# MCU_144.net
KiCad netlist of a schematic drawn in Altium Designer
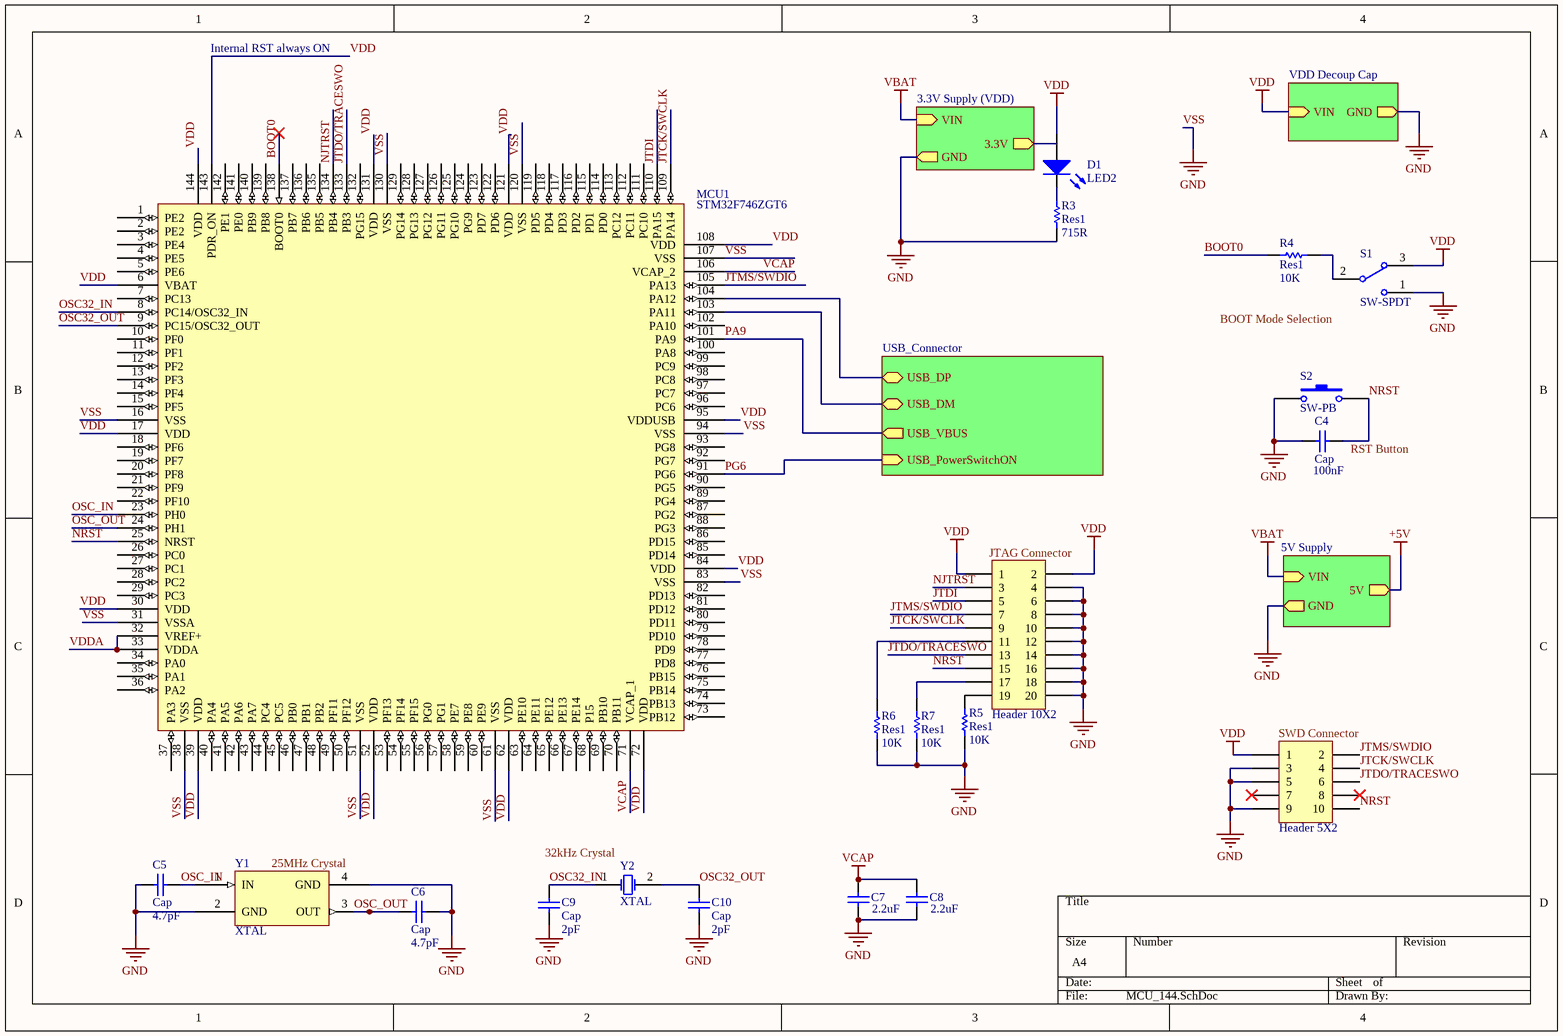
[diagram p0: MCU_144.SchDoc]

(export (version "E")
  (design (tool "Eeschema 10.0.6"))
  (components
    (comp (ref "C4")
      (value "Cap")
      (footprint "0402")
      (description "Multilayer Ceramic Capacitors MLCC - SMD/SMT 16volts 0.1uF 20% X7R")
      (fields (field (name "ALTIUM_VALUE") "100nF"))
      (libsource (lib "Miscellaneous Devices") (part "Cap"))
    )
    (comp (ref "C5")
      (value "Cap")
      (footprint "RAD-0.3")
      (description "Capacitor")
      (fields (field (name "ALTIUM_VALUE") "4.7pF") (field (name "PUBLISHER") "Altium Limited"))
      (libsource (lib "Miscellaneous Devices") (part "Cap"))
    )
    (comp (ref "C6")
      (value "Cap")
      (footprint "RAD-0.3")
      (description "Capacitor")
      (fields (field (name "ALTIUM_VALUE") "4.7pF") (field (name "PUBLISHER") "Altium Limited"))
      (libsource (lib "Miscellaneous Devices") (part "Cap"))
    )
    (comp (ref "C7")
      (value "2.2uF")
      (footprint "0402")
      (description "Multilayer Ceramic Capacitors MLCC - SMD/SMT 0402 2.2uF 6.3volts X5R 10%")
      (fields (field (name "Comment") "Cap"))
      (libsource (lib "Miscellaneous Devices") (part "Cap"))
    )
    (comp (ref "C8")
      (value "2.2uF")
      (footprint "0402")
      (description "Multilayer Ceramic Capacitors MLCC - SMD/SMT 0402 2.2uF 6.3volts X5R 10%")
      (fields (field (name "Comment") "Cap"))
      (libsource (lib "Miscellaneous Devices") (part "Cap"))
    )
    (comp (ref "C9")
      (value "Cap")
      (footprint "RAD-0.3")
      (description "Capacitor")
      (fields (field (name "ALTIUM_VALUE") "2pF") (field (name "PUBLISHER") "Altium Limited"))
      (libsource (lib "Miscellaneous Devices") (part "Cap"))
    )
    (comp (ref "C10")
      (value "Cap")
      (footprint "RAD-0.3")
      (description "Capacitor")
      (fields (field (name "ALTIUM_VALUE") "2pF") (field (name "PUBLISHER") "Altium Limited"))
      (libsource (lib "Miscellaneous Devices") (part "Cap"))
    )
    (comp (ref "D1")
      (value "LED2")
      (footprint "3.2X1.6X1.1")
      (description "Typical RED, GREEN, YELLOW, AMBER GaAs LED")
      (fields (field (name "PUBLISHER") "Altium Limited"))
      (libsource (lib "Miscellaneous Devices") (part "LED2"))
    )
    (comp (ref "MCU1")
      (value "STM32F746ZGT6")
      (footprint "LQFP144")
      (libsource (lib "MainboardSchLib") (part "STM32F746ZGT6"))
    )
    (comp (ref "P1")
      (value "Header 10X2")
      (footprint "HDR2X10")
      (description "Header, 10-Pin, Dual row")
      (fields (field (name "PUBLISHER") "Altium Limited"))
      (libsource (lib "Miscellaneous Connectors") (part "Header 10X2"))
    )
    (comp (ref "P2")
      (value "Header 5X2")
      (footprint "HDR2X5")
      (description "Header, 5-Pin, Dual row")
      (fields (field (name "PUBLISHER") "Altium Limited"))
      (libsource (lib "Miscellaneous Connectors") (part "Header 5X2"))
    )
    (comp (ref "R3")
      (value "Res1")
      (footprint "AXIAL-0.3")
      (description "Resistor")
      (fields (field (name "ALTIUM_VALUE") "715R") (field (name "PUBLISHER") "Altium Limited"))
      (libsource (lib "Miscellaneous Devices") (part "Res1"))
    )
    (comp (ref "R4")
      (value "Res1")
      (footprint "RES0402")
      (description "Thick Film Resistors - SMD 0.2watt 10Kohms 1% 100ppm")
      (fields (field (name "ALTIUM_VALUE") "10K"))
      (libsource (lib "Miscellaneous Devices") (part "Res1"))
    )
    (comp (ref "R5")
      (value "Res1")
      (footprint "RES0402")
      (description "Thick Film Resistors - SMD 0.2watt 10Kohms 1% 100ppm")
      (fields (field (name "ALTIUM_VALUE") "10K"))
      (libsource (lib "Miscellaneous Devices") (part "Res1"))
    )
    (comp (ref "R6")
      (value "Res1")
      (footprint "RES0402")
      (description "Thick Film Resistors - SMD 0.2watt 10Kohms 1% 100ppm")
      (fields (field (name "ALTIUM_VALUE") "10K"))
      (libsource (lib "Miscellaneous Devices") (part "Res1"))
    )
    (comp (ref "R7")
      (value "Res1")
      (footprint "RES0402")
      (description "Thick Film Resistors - SMD 0.2watt 10Kohms 1% 100ppm")
      (fields (field (name "ALTIUM_VALUE") "10K"))
      (libsource (lib "Miscellaneous Devices") (part "Res1"))
    )
    (comp (ref "S1")
      (value "SW-SPDT")
      (footprint "TL36WW15050")
      (description "SPDT Subminiature Toggle Switch, Right Angle Mounting, Vertical Actuation")
      (fields (field (name "PUBLISHER") "Altium Limited"))
      (libsource (lib "Miscellaneous Devices") (part "SW-SPDT"))
    )
    (comp (ref "S2")
      (value "SW-PB")
      (footprint "SPST-2")
      (description "Switch")
      (fields (field (name "PUBLISHER") "Altium Limited"))
      (libsource (lib "Miscellaneous Devices") (part "SW-PB"))
    )
    (comp (ref "Y1")
      (value "XTAL")
      (description "25MHz Crystal Oscilator")
      (libsource (lib "MainboardSchLib") (part "ECX-2236Q"))
    )
    (comp (ref "Y2")
      (value "XTAL")
      (footprint "R38")
      (description "Crystal Oscillator")
      (fields (field (name "PUBLISHER") "Altium Limited"))
      (libsource (lib "Miscellaneous Devices") (part "XTAL"))
    )
  )
  (nets
    (net (code "3") (name "/BOOT0") (class "Default")
      (node (ref "MCU1") (pin "138") (pinfunction "BOOT0_138") (pintype "input"))
      (node (ref "R4") (pin "2") (pinfunction "2_2") (pintype "passive"))
    )
    (net (code "4") (name "/JTCK{slash}SWCLK") (class "Default")
      (node (ref "MCU1") (pin "109") (pinfunction "PA14_109") (pintype "bidirectional"))
      (node (ref "P1") (pin "9") (pinfunction "9_9") (pintype "passive"))
      (node (ref "P2") (pin "4") (pinfunction "4_4") (pintype "passive"))
    )
    (net (code "5") (name "/JTDI") (class "Default")
      (node (ref "MCU1") (pin "110") (pinfunction "PA15_110") (pintype "bidirectional"))
      (node (ref "P1") (pin "5") (pinfunction "5_5") (pintype "passive"))
    )
    (net (code "6") (name "/JTDO{slash}TRACESWO") (class "Default")
      (node (ref "MCU1") (pin "133") (pinfunction "PB3_133") (pintype "bidirectional"))
      (node (ref "P1") (pin "13") (pinfunction "13_13") (pintype "passive"))
      (node (ref "P2") (pin "6") (pinfunction "6_6") (pintype "passive"))
    )
    (net (code "7") (name "/JTMS{slash}SWDIO") (class "Default")
      (node (ref "MCU1") (pin "105") (pinfunction "PA13_105") (pintype "bidirectional"))
      (node (ref "P1") (pin "7") (pinfunction "7_7") (pintype "passive"))
      (node (ref "P2") (pin "2") (pinfunction "2_2") (pintype "passive"))
    )
    (net (code "8") (name "/NJTRST") (class "Default")
      (node (ref "MCU1") (pin "134") (pinfunction "PB4_134") (pintype "bidirectional"))
      (node (ref "P1") (pin "3") (pinfunction "3_3") (pintype "passive"))
    )
    (net (code "9") (name "/NRST") (class "Default")
      (node (ref "C4") (pin "2") (pinfunction "2_2") (pintype "passive"))
      (node (ref "MCU1") (pin "25") (pinfunction "NRST_25") (pintype "bidirectional"))
      (node (ref "P1") (pin "15") (pinfunction "15_15") (pintype "passive"))
      (node (ref "P2") (pin "10") (pinfunction "10_10") (pintype "passive"))
      (node (ref "S2") (pin "2") (pinfunction "2_2") (pintype "passive"))
    )
    (net (code "10") (name "/OSC32_IN") (class "Default")
      (node (ref "C9") (pin "2") (pinfunction "2_2") (pintype "passive"))
      (node (ref "MCU1") (pin "8") (pinfunction "PC14/OSC32_IN_8") (pintype "bidirectional"))
      (node (ref "Y2") (pin "1") (pinfunction "OSC1_1") (pintype "passive"))
    )
    (net (code "11") (name "/OSC32_OUT") (class "Default")
      (node (ref "C10") (pin "2") (pinfunction "2_2") (pintype "passive"))
      (node (ref "MCU1") (pin "9") (pinfunction "PC15/OSC32_OUT_9") (pintype "bidirectional"))
      (node (ref "Y2") (pin "2") (pinfunction "OSC2_2") (pintype "passive"))
    )
    (net (code "12") (name "/OSC_IN") (class "Default")
      (node (ref "C5") (pin "1") (pinfunction "1_1") (pintype "passive"))
      (node (ref "MCU1") (pin "23") (pinfunction "PH0_23") (pintype "bidirectional"))
      (node (ref "Y1") (pin "1") (pinfunction "IN_1") (pintype "input"))
    )
    (net (code "13") (name "/OSC_OUT") (class "Default")
      (node (ref "C6") (pin "2") (pinfunction "2_2") (pintype "passive"))
      (node (ref "MCU1") (pin "24") (pinfunction "PH1_24") (pintype "bidirectional"))
      (node (ref "Y1") (pin "3") (pinfunction "OUT_3") (pintype "output"))
    )
    (net (code "14") (name "/PA9") (class "Default")
      (node (ref "MCU1") (pin "101") (pinfunction "PA9_101") (pintype "bidirectional"))
    )
    (net (code "15") (name "/PG6") (class "Default")
      (node (ref "MCU1") (pin "91") (pinfunction "PG6_91") (pintype "bidirectional"))
    )
    (net (code "16") (name "/USB_DM") (class "Default")
      (node (ref "MCU1") (pin "103") (pinfunction "PA11_103") (pintype "bidirectional"))
    )
    (net (code "17") (name "/USB_DP") (class "Default")
      (node (ref "MCU1") (pin "104") (pinfunction "PA12_104") (pintype "bidirectional"))
    )
    (net (code "18") (name "/VDDA") (class "Default")
      (node (ref "MCU1") (pin "32") (pinfunction "VREF+_32") (pintype "power_in"))
      (node (ref "MCU1") (pin "33") (pinfunction "VDDA_33") (pintype "power_in"))
    )
    (net (code "19") (name "GND") (class "Default")
      (node (ref "C10") (pin "1") (pinfunction "1_1") (pintype "passive"))
      (node (ref "C4") (pin "1") (pinfunction "1_1") (pintype "passive"))
      (node (ref "C5") (pin "2") (pinfunction "2_2") (pintype "passive"))
      (node (ref "C6") (pin "1") (pinfunction "1_1") (pintype "passive"))
      (node (ref "C7") (pin "1") (pinfunction "1_1") (pintype "passive"))
      (node (ref "C8") (pin "1") (pinfunction "1_1") (pintype "passive"))
      (node (ref "C9") (pin "1") (pinfunction "1_1") (pintype "passive"))
      (node (ref "MCU1") (pin "107") (pinfunction "VSS_107") (pintype "power_in"))
      (node (ref "MCU1") (pin "120") (pinfunction "VSS_120") (pintype "power_in"))
      (node (ref "MCU1") (pin "130") (pinfunction "VSS_130") (pintype "power_in"))
      (node (ref "MCU1") (pin "16") (pinfunction "VSS_16") (pintype "power_in"))
      (node (ref "MCU1") (pin "31") (pinfunction "VSSA_31") (pintype "power_in"))
      (node (ref "MCU1") (pin "38") (pinfunction "VSS_38") (pintype "power_in"))
      (node (ref "MCU1") (pin "51") (pinfunction "VSS_51") (pintype "power_in"))
      (node (ref "MCU1") (pin "61") (pinfunction "VSS_61") (pintype "power_in"))
      (node (ref "MCU1") (pin "83") (pinfunction "VSS_83") (pintype "power_in"))
      (node (ref "MCU1") (pin "94") (pinfunction "VSS_94") (pintype "power_in"))
      (node (ref "P1") (pin "10") (pinfunction "10_10") (pintype "passive"))
      (node (ref "P1") (pin "12") (pinfunction "12_12") (pintype "passive"))
      (node (ref "P1") (pin "14") (pinfunction "14_14") (pintype "passive"))
      (node (ref "P1") (pin "16") (pinfunction "16_16") (pintype "passive"))
      (node (ref "P1") (pin "18") (pinfunction "18_18") (pintype "passive"))
      (node (ref "P1") (pin "20") (pinfunction "20_20") (pintype "passive"))
      (node (ref "P1") (pin "4") (pinfunction "4_4") (pintype "passive"))
      (node (ref "P1") (pin "6") (pinfunction "6_6") (pintype "passive"))
      (node (ref "P1") (pin "8") (pinfunction "8_8") (pintype "passive"))
      (node (ref "P2") (pin "3") (pinfunction "3_3") (pintype "passive"))
      (node (ref "P2") (pin "5") (pinfunction "5_5") (pintype "passive"))
      (node (ref "P2") (pin "9") (pinfunction "9_9") (pintype "passive"))
      (node (ref "R3") (pin "1") (pinfunction "1_1") (pintype "passive"))
      (node (ref "R5") (pin "1") (pinfunction "1_1") (pintype "passive"))
      (node (ref "R6") (pin "1") (pinfunction "1_1") (pintype "passive"))
      (node (ref "R7") (pin "1") (pinfunction "1_1") (pintype "passive"))
      (node (ref "S1") (pin "1") (pinfunction "1_1") (pintype "passive"))
      (node (ref "S2") (pin "1") (pinfunction "1_1") (pintype "passive"))
      (node (ref "Y1") (pin "2") (pinfunction "GND_2") (pintype "power_in"))
      (node (ref "Y1") (pin "4") (pinfunction "GND_4") (pintype "power_in"))
    )
    (net (code "20") (name "Net-(D1-K)") (class "Default")
      (node (ref "D1") (pin "2") (pinfunction "K_2") (pintype "passive"))
      (node (ref "R3") (pin "2") (pinfunction "2_2") (pintype "passive"))
    )
    (net (code "21") (name "Net-(P1-Pad11)") (class "Default")
      (node (ref "P1") (pin "11") (pinfunction "11_11") (pintype "passive"))
      (node (ref "R6") (pin "2") (pinfunction "2_2") (pintype "passive"))
    )
    (net (code "22") (name "Net-(P1-Pad17)") (class "Default")
      (node (ref "P1") (pin "17") (pinfunction "17_17") (pintype "passive"))
      (node (ref "R7") (pin "2") (pinfunction "2_2") (pintype "passive"))
    )
    (net (code "23") (name "Net-(P1-Pad19)") (class "Default")
      (node (ref "P1") (pin "19") (pinfunction "19_19") (pintype "passive"))
      (node (ref "R5") (pin "2") (pinfunction "2_2") (pintype "passive"))
    )
    (net (code "24") (name "Net-(R4-Pad1)") (class "Default")
      (node (ref "R4") (pin "1") (pinfunction "1_1") (pintype "passive"))
      (node (ref "S1") (pin "2") (pinfunction "2_2") (pintype "passive"))
    )
    (net (code "26") (name "VCAP") (class "Default")
      (node (ref "C7") (pin "2") (pinfunction "2_2") (pintype "passive"))
      (node (ref "C8") (pin "2") (pinfunction "2_2") (pintype "passive"))
      (node (ref "MCU1") (pin "106") (pinfunction "VCAP_2_106") (pintype "power_in"))
      (node (ref "MCU1") (pin "71") (pinfunction "VCAP_1_71") (pintype "power_in"))
    )
    (net (code "27") (name "VDD") (class "Default")
      (node (ref "D1") (pin "1") (pinfunction "A_1") (pintype "passive"))
      (node (ref "MCU1") (pin "108") (pinfunction "VDD_108") (pintype "power_in"))
      (node (ref "MCU1") (pin "121") (pinfunction "VDD_121") (pintype "power_in"))
      (node (ref "MCU1") (pin "131") (pinfunction "VDD_131") (pintype "power_in"))
      (node (ref "MCU1") (pin "143") (pinfunction "PDR_ON_143") (pintype "power_in"))
      (node (ref "MCU1") (pin "144") (pinfunction "VDD_144") (pintype "power_in"))
      (node (ref "MCU1") (pin "17") (pinfunction "VDD_17") (pintype "power_in"))
      (node (ref "MCU1") (pin "30") (pinfunction "VDD_30") (pintype "power_in"))
      (node (ref "MCU1") (pin "39") (pinfunction "VDD_39") (pintype "power_in"))
      (node (ref "MCU1") (pin "52") (pinfunction "VDD_52") (pintype "power_in"))
      (node (ref "MCU1") (pin "6") (pinfunction "VBAT_6") (pintype "power_in"))
      (node (ref "MCU1") (pin "62") (pinfunction "VDD_62") (pintype "power_in"))
      (node (ref "MCU1") (pin "72") (pinfunction "VDD_72") (pintype "power_in"))
      (node (ref "MCU1") (pin "84") (pinfunction "VDD_84") (pintype "power_in"))
      (node (ref "MCU1") (pin "95") (pinfunction "VDDUSB_95") (pintype "power_in"))
      (node (ref "P1") (pin "1") (pinfunction "1_1") (pintype "passive"))
      (node (ref "P1") (pin "2") (pinfunction "2_2") (pintype "passive"))
      (node (ref "P2") (pin "1") (pinfunction "1_1") (pintype "passive"))
      (node (ref "S1") (pin "3") (pinfunction "3_3") (pintype "passive"))
    )
    (net (code "28") (name "unconnected-(MCU1-P15-Pad68)") (class "Default")
      (node (ref "MCU1") (pin "68") (pinfunction "P15_68") (pintype "bidirectional"))
    )
    (net (code "29") (name "unconnected-(MCU1-PA0-Pad34)") (class "Default")
      (node (ref "MCU1") (pin "34") (pinfunction "PA0_34") (pintype "bidirectional"))
    )
    (net (code "30") (name "unconnected-(MCU1-PA1-Pad35)") (class "Default")
      (node (ref "MCU1") (pin "35") (pinfunction "PA1_35") (pintype "bidirectional"))
    )
    (net (code "31") (name "unconnected-(MCU1-PA2-Pad36)") (class "Default")
      (node (ref "MCU1") (pin "36") (pinfunction "PA2_36") (pintype "bidirectional"))
    )
    (net (code "32") (name "unconnected-(MCU1-PA3-Pad37)") (class "Default")
      (node (ref "MCU1") (pin "37") (pinfunction "PA3_37") (pintype "bidirectional"))
    )
    (net (code "33") (name "unconnected-(MCU1-PA4-Pad40)") (class "Default")
      (node (ref "MCU1") (pin "40") (pinfunction "PA4_40") (pintype "bidirectional"))
    )
    (net (code "34") (name "unconnected-(MCU1-PA5-Pad41)") (class "Default")
      (node (ref "MCU1") (pin "41") (pinfunction "PA5_41") (pintype "bidirectional"))
    )
    (net (code "35") (name "unconnected-(MCU1-PA6-Pad42)") (class "Default")
      (node (ref "MCU1") (pin "42") (pinfunction "PA6_42") (pintype "bidirectional"))
    )
    (net (code "36") (name "unconnected-(MCU1-PA7-Pad43)") (class "Default")
      (node (ref "MCU1") (pin "43") (pinfunction "PA7_43") (pintype "bidirectional"))
    )
    (net (code "37") (name "unconnected-(MCU1-PA8-Pad100)") (class "Default")
      (node (ref "MCU1") (pin "100") (pinfunction "PA8_100") (pintype "bidirectional"))
    )
    (net (code "38") (name "unconnected-(MCU1-PA10-Pad102)") (class "Default")
      (node (ref "MCU1") (pin "102") (pinfunction "PA10_102") (pintype "bidirectional"))
    )
    (net (code "39") (name "unconnected-(MCU1-PB0-Pad46)") (class "Default")
      (node (ref "MCU1") (pin "46") (pinfunction "PB0_46") (pintype "bidirectional"))
    )
    (net (code "40") (name "unconnected-(MCU1-PB1-Pad47)") (class "Default")
      (node (ref "MCU1") (pin "47") (pinfunction "PB1_47") (pintype "bidirectional"))
    )
    (net (code "41") (name "unconnected-(MCU1-PB2-Pad48)") (class "Default")
      (node (ref "MCU1") (pin "48") (pinfunction "PB2_48") (pintype "bidirectional"))
    )
    (net (code "42") (name "unconnected-(MCU1-PB5-Pad135)") (class "Default")
      (node (ref "MCU1") (pin "135") (pinfunction "PB5_135") (pintype "bidirectional"))
    )
    (net (code "43") (name "unconnected-(MCU1-PB6-Pad136)") (class "Default")
      (node (ref "MCU1") (pin "136") (pinfunction "PB6_136") (pintype "bidirectional"))
    )
    (net (code "44") (name "unconnected-(MCU1-PB7-Pad137)") (class "Default")
      (node (ref "MCU1") (pin "137") (pinfunction "PB7_137") (pintype "bidirectional"))
    )
    (net (code "45") (name "unconnected-(MCU1-PB8-Pad139)") (class "Default")
      (node (ref "MCU1") (pin "139") (pinfunction "PB8_139") (pintype "bidirectional"))
    )
    (net (code "46") (name "unconnected-(MCU1-PB9-Pad140)") (class "Default")
      (node (ref "MCU1") (pin "140") (pinfunction "PB9_140") (pintype "bidirectional"))
    )
    (net (code "47") (name "unconnected-(MCU1-PB10-Pad69)") (class "Default")
      (node (ref "MCU1") (pin "69") (pinfunction "PB10_69") (pintype "bidirectional"))
    )
    (net (code "48") (name "unconnected-(MCU1-PB11-Pad70)") (class "Default")
      (node (ref "MCU1") (pin "70") (pinfunction "PB11_70") (pintype "bidirectional"))
    )
    (net (code "49") (name "unconnected-(MCU1-PB12-Pad73)") (class "Default")
      (node (ref "MCU1") (pin "73") (pinfunction "PB12_73") (pintype "bidirectional"))
    )
    (net (code "50") (name "unconnected-(MCU1-PB13-Pad74)") (class "Default")
      (node (ref "MCU1") (pin "74") (pinfunction "PB13_74") (pintype "bidirectional"))
    )
    (net (code "51") (name "unconnected-(MCU1-PB14-Pad75)") (class "Default")
      (node (ref "MCU1") (pin "75") (pinfunction "PB14_75") (pintype "bidirectional"))
    )
    (net (code "52") (name "unconnected-(MCU1-PB15-Pad76)") (class "Default")
      (node (ref "MCU1") (pin "76") (pinfunction "PB15_76") (pintype "bidirectional"))
    )
    (net (code "53") (name "unconnected-(MCU1-PC0-Pad26)") (class "Default")
      (node (ref "MCU1") (pin "26") (pinfunction "PC0_26") (pintype "bidirectional"))
    )
    (net (code "54") (name "unconnected-(MCU1-PC1-Pad27)") (class "Default")
      (node (ref "MCU1") (pin "27") (pinfunction "PC1_27") (pintype "bidirectional"))
    )
    (net (code "55") (name "unconnected-(MCU1-PC2-Pad28)") (class "Default")
      (node (ref "MCU1") (pin "28") (pinfunction "PC2_28") (pintype "bidirectional"))
    )
    (net (code "56") (name "unconnected-(MCU1-PC3-Pad29)") (class "Default")
      (node (ref "MCU1") (pin "29") (pinfunction "PC3_29") (pintype "bidirectional"))
    )
    (net (code "57") (name "unconnected-(MCU1-PC4-Pad44)") (class "Default")
      (node (ref "MCU1") (pin "44") (pinfunction "PC4_44") (pintype "bidirectional"))
    )
    (net (code "58") (name "unconnected-(MCU1-PC5-Pad45)") (class "Default")
      (node (ref "MCU1") (pin "45") (pinfunction "PC5_45") (pintype "bidirectional"))
    )
    (net (code "59") (name "unconnected-(MCU1-PC6-Pad96)") (class "Default")
      (node (ref "MCU1") (pin "96") (pinfunction "PC6_96") (pintype "bidirectional"))
    )
    (net (code "60") (name "unconnected-(MCU1-PC7-Pad97)") (class "Default")
      (node (ref "MCU1") (pin "97") (pinfunction "PC7_97") (pintype "bidirectional"))
    )
    (net (code "61") (name "unconnected-(MCU1-PC8-Pad98)") (class "Default")
      (node (ref "MCU1") (pin "98") (pinfunction "PC8_98") (pintype "bidirectional"))
    )
    (net (code "62") (name "unconnected-(MCU1-PC9-Pad99)") (class "Default")
      (node (ref "MCU1") (pin "99") (pinfunction "PC9_99") (pintype "bidirectional"))
    )
    (net (code "63") (name "unconnected-(MCU1-PC10-Pad111)") (class "Default")
      (node (ref "MCU1") (pin "111") (pinfunction "PC10_111") (pintype "bidirectional"))
    )
    (net (code "64") (name "unconnected-(MCU1-PC11-Pad112)") (class "Default")
      (node (ref "MCU1") (pin "112") (pinfunction "PC11_112") (pintype "bidirectional"))
    )
    (net (code "65") (name "unconnected-(MCU1-PC12-Pad113)") (class "Default")
      (node (ref "MCU1") (pin "113") (pinfunction "PC12_113") (pintype "bidirectional"))
    )
    (net (code "66") (name "unconnected-(MCU1-PC13-Pad7)") (class "Default")
      (node (ref "MCU1") (pin "7") (pinfunction "PC13_7") (pintype "bidirectional"))
    )
    (net (code "67") (name "unconnected-(MCU1-PD0-Pad114)") (class "Default")
      (node (ref "MCU1") (pin "114") (pinfunction "PD0_114") (pintype "bidirectional"))
    )
    (net (code "68") (name "unconnected-(MCU1-PD1-Pad115)") (class "Default")
      (node (ref "MCU1") (pin "115") (pinfunction "PD1_115") (pintype "bidirectional"))
    )
    (net (code "69") (name "unconnected-(MCU1-PD2-Pad116)") (class "Default")
      (node (ref "MCU1") (pin "116") (pinfunction "PD2_116") (pintype "bidirectional"))
    )
    (net (code "70") (name "unconnected-(MCU1-PD3-Pad117)") (class "Default")
      (node (ref "MCU1") (pin "117") (pinfunction "PD3_117") (pintype "bidirectional"))
    )
    (net (code "71") (name "unconnected-(MCU1-PD4-Pad118)") (class "Default")
      (node (ref "MCU1") (pin "118") (pinfunction "PD4_118") (pintype "bidirectional"))
    )
    (net (code "72") (name "unconnected-(MCU1-PD5-Pad119)") (class "Default")
      (node (ref "MCU1") (pin "119") (pinfunction "PD5_119") (pintype "bidirectional"))
    )
    (net (code "73") (name "unconnected-(MCU1-PD6-Pad122)") (class "Default")
      (node (ref "MCU1") (pin "122") (pinfunction "PD6_122") (pintype "bidirectional"))
    )
    (net (code "74") (name "unconnected-(MCU1-PD7-Pad123)") (class "Default")
      (node (ref "MCU1") (pin "123") (pinfunction "PD7_123") (pintype "bidirectional"))
    )
    (net (code "75") (name "unconnected-(MCU1-PD8-Pad77)") (class "Default")
      (node (ref "MCU1") (pin "77") (pinfunction "PD8_77") (pintype "bidirectional"))
    )
    (net (code "76") (name "unconnected-(MCU1-PD9-Pad78)") (class "Default")
      (node (ref "MCU1") (pin "78") (pinfunction "PD9_78") (pintype "bidirectional"))
    )
    (net (code "77") (name "unconnected-(MCU1-PD10-Pad79)") (class "Default")
      (node (ref "MCU1") (pin "79") (pinfunction "PD10_79") (pintype "bidirectional"))
    )
    (net (code "78") (name "unconnected-(MCU1-PD11-Pad80)") (class "Default")
      (node (ref "MCU1") (pin "80") (pinfunction "PD11_80") (pintype "bidirectional"))
    )
    (net (code "79") (name "unconnected-(MCU1-PD12-Pad81)") (class "Default")
      (node (ref "MCU1") (pin "81") (pinfunction "PD12_81") (pintype "bidirectional"))
    )
    (net (code "80") (name "unconnected-(MCU1-PD13-Pad82)") (class "Default")
      (node (ref "MCU1") (pin "82") (pinfunction "PD13_82") (pintype "bidirectional"))
    )
    (net (code "81") (name "unconnected-(MCU1-PD14-Pad85)") (class "Default")
      (node (ref "MCU1") (pin "85") (pinfunction "PD14_85") (pintype "bidirectional"))
    )
    (net (code "82") (name "unconnected-(MCU1-PD15-Pad86)") (class "Default")
      (node (ref "MCU1") (pin "86") (pinfunction "PD15_86") (pintype "bidirectional"))
    )
    (net (code "83") (name "unconnected-(MCU1-PE0-Pad141)") (class "Default")
      (node (ref "MCU1") (pin "141") (pinfunction "PE0_141") (pintype "bidirectional"))
    )
    (net (code "84") (name "unconnected-(MCU1-PE1-Pad142)") (class "Default")
      (node (ref "MCU1") (pin "142") (pinfunction "PE1_142") (pintype "bidirectional"))
    )
    (net (code "85") (name "unconnected-(MCU1-PE2-Pad1)") (class "Default")
      (node (ref "MCU1") (pin "1") (pinfunction "PE2_1") (pintype "bidirectional"))
    )
    (net (code "86") (name "unconnected-(MCU1-PE2-Pad2)") (class "Default")
      (node (ref "MCU1") (pin "2") (pinfunction "PE2_2") (pintype "bidirectional"))
    )
    (net (code "87") (name "unconnected-(MCU1-PE4-Pad3)") (class "Default")
      (node (ref "MCU1") (pin "3") (pinfunction "PE4_3") (pintype "bidirectional"))
    )
    (net (code "88") (name "unconnected-(MCU1-PE5-Pad4)") (class "Default")
      (node (ref "MCU1") (pin "4") (pinfunction "PE5_4") (pintype "bidirectional"))
    )
    (net (code "89") (name "unconnected-(MCU1-PE6-Pad5)") (class "Default")
      (node (ref "MCU1") (pin "5") (pinfunction "PE6_5") (pintype "bidirectional"))
    )
    (net (code "90") (name "unconnected-(MCU1-PE7-Pad58)") (class "Default")
      (node (ref "MCU1") (pin "58") (pinfunction "PE7_58") (pintype "bidirectional"))
    )
    (net (code "91") (name "unconnected-(MCU1-PE8-Pad59)") (class "Default")
      (node (ref "MCU1") (pin "59") (pinfunction "PE8_59") (pintype "bidirectional"))
    )
    (net (code "92") (name "unconnected-(MCU1-PE9-Pad60)") (class "Default")
      (node (ref "MCU1") (pin "60") (pinfunction "PE9_60") (pintype "bidirectional"))
    )
    (net (code "93") (name "unconnected-(MCU1-PE10-Pad63)") (class "Default")
      (node (ref "MCU1") (pin "63") (pinfunction "PE10_63") (pintype "bidirectional"))
    )
    (net (code "94") (name "unconnected-(MCU1-PE11-Pad64)") (class "Default")
      (node (ref "MCU1") (pin "64") (pinfunction "PE11_64") (pintype "bidirectional"))
    )
    (net (code "95") (name "unconnected-(MCU1-PE12-Pad65)") (class "Default")
      (node (ref "MCU1") (pin "65") (pinfunction "PE12_65") (pintype "bidirectional"))
    )
    (net (code "96") (name "unconnected-(MCU1-PE13-Pad66)") (class "Default")
      (node (ref "MCU1") (pin "66") (pinfunction "PE13_66") (pintype "bidirectional"))
    )
    (net (code "97") (name "unconnected-(MCU1-PE14-Pad67)") (class "Default")
      (node (ref "MCU1") (pin "67") (pinfunction "PE14_67") (pintype "bidirectional"))
    )
    (net (code "98") (name "unconnected-(MCU1-PF0-Pad10)") (class "Default")
      (node (ref "MCU1") (pin "10") (pinfunction "PF0_10") (pintype "bidirectional"))
    )
    (net (code "99") (name "unconnected-(MCU1-PF1-Pad11)") (class "Default")
      (node (ref "MCU1") (pin "11") (pinfunction "PF1_11") (pintype "bidirectional"))
    )
    (net (code "100") (name "unconnected-(MCU1-PF2-Pad12)") (class "Default")
      (node (ref "MCU1") (pin "12") (pinfunction "PF2_12") (pintype "bidirectional"))
    )
    (net (code "101") (name "unconnected-(MCU1-PF3-Pad13)") (class "Default")
      (node (ref "MCU1") (pin "13") (pinfunction "PF3_13") (pintype "bidirectional"))
    )
    (net (code "102") (name "unconnected-(MCU1-PF4-Pad14)") (class "Default")
      (node (ref "MCU1") (pin "14") (pinfunction "PF4_14") (pintype "bidirectional"))
    )
    (net (code "103") (name "unconnected-(MCU1-PF5-Pad15)") (class "Default")
      (node (ref "MCU1") (pin "15") (pinfunction "PF5_15") (pintype "bidirectional"))
    )
    (net (code "104") (name "unconnected-(MCU1-PF6-Pad18)") (class "Default")
      (node (ref "MCU1") (pin "18") (pinfunction "PF6_18") (pintype "bidirectional"))
    )
    (net (code "105") (name "unconnected-(MCU1-PF7-Pad19)") (class "Default")
      (node (ref "MCU1") (pin "19") (pinfunction "PF7_19") (pintype "bidirectional"))
    )
    (net (code "106") (name "unconnected-(MCU1-PF8-Pad20)") (class "Default")
      (node (ref "MCU1") (pin "20") (pinfunction "PF8_20") (pintype "bidirectional"))
    )
    (net (code "107") (name "unconnected-(MCU1-PF9-Pad21)") (class "Default")
      (node (ref "MCU1") (pin "21") (pinfunction "PF9_21") (pintype "bidirectional"))
    )
    (net (code "108") (name "unconnected-(MCU1-PF10-Pad22)") (class "Default")
      (node (ref "MCU1") (pin "22") (pinfunction "PF10_22") (pintype "bidirectional"))
    )
    (net (code "109") (name "unconnected-(MCU1-PF11-Pad49)") (class "Default")
      (node (ref "MCU1") (pin "49") (pinfunction "PF11_49") (pintype "bidirectional"))
    )
    (net (code "110") (name "unconnected-(MCU1-PF12-Pad50)") (class "Default")
      (node (ref "MCU1") (pin "50") (pinfunction "PF12_50") (pintype "bidirectional"))
    )
    (net (code "111") (name "unconnected-(MCU1-PF13-Pad53)") (class "Default")
      (node (ref "MCU1") (pin "53") (pinfunction "PF13_53") (pintype "bidirectional"))
    )
    (net (code "112") (name "unconnected-(MCU1-PF14-Pad54)") (class "Default")
      (node (ref "MCU1") (pin "54") (pinfunction "PF14_54") (pintype "bidirectional"))
    )
    (net (code "113") (name "unconnected-(MCU1-PF15-Pad55)") (class "Default")
      (node (ref "MCU1") (pin "55") (pinfunction "PF15_55") (pintype "bidirectional"))
    )
    (net (code "114") (name "unconnected-(MCU1-PG0-Pad56)") (class "Default")
      (node (ref "MCU1") (pin "56") (pinfunction "PG0_56") (pintype "bidirectional"))
    )
    (net (code "115") (name "unconnected-(MCU1-PG1-Pad57)") (class "Default")
      (node (ref "MCU1") (pin "57") (pinfunction "PG1_57") (pintype "bidirectional"))
    )
    (net (code "116") (name "unconnected-(MCU1-PG2-Pad87)") (class "Default")
      (node (ref "MCU1") (pin "87") (pinfunction "PG2_87") (pintype "bidirectional"))
    )
    (net (code "117") (name "unconnected-(MCU1-PG3-Pad88)") (class "Default")
      (node (ref "MCU1") (pin "88") (pinfunction "PG3_88") (pintype "bidirectional"))
    )
    (net (code "118") (name "unconnected-(MCU1-PG4-Pad89)") (class "Default")
      (node (ref "MCU1") (pin "89") (pinfunction "PG4_89") (pintype "bidirectional"))
    )
    (net (code "119") (name "unconnected-(MCU1-PG5-Pad90)") (class "Default")
      (node (ref "MCU1") (pin "90") (pinfunction "PG5_90") (pintype "bidirectional"))
    )
    (net (code "120") (name "unconnected-(MCU1-PG7-Pad92)") (class "Default")
      (node (ref "MCU1") (pin "92") (pinfunction "PG7_92") (pintype "bidirectional"))
    )
    (net (code "121") (name "unconnected-(MCU1-PG8-Pad93)") (class "Default")
      (node (ref "MCU1") (pin "93") (pinfunction "PG8_93") (pintype "bidirectional"))
    )
    (net (code "122") (name "unconnected-(MCU1-PG9-Pad124)") (class "Default")
      (node (ref "MCU1") (pin "124") (pinfunction "PG9_124") (pintype "bidirectional"))
    )
    (net (code "123") (name "unconnected-(MCU1-PG10-Pad125)") (class "Default")
      (node (ref "MCU1") (pin "125") (pinfunction "PG10_125") (pintype "bidirectional"))
    )
    (net (code "124") (name "unconnected-(MCU1-PG11-Pad126)") (class "Default")
      (node (ref "MCU1") (pin "126") (pinfunction "PG11_126") (pintype "bidirectional"))
    )
    (net (code "125") (name "unconnected-(MCU1-PG12-Pad127)") (class "Default")
      (node (ref "MCU1") (pin "127") (pinfunction "PG12_127") (pintype "bidirectional"))
    )
    (net (code "126") (name "unconnected-(MCU1-PG13-Pad128)") (class "Default")
      (node (ref "MCU1") (pin "128") (pinfunction "PG13_128") (pintype "bidirectional"))
    )
    (net (code "127") (name "unconnected-(MCU1-PG14-Pad129)") (class "Default")
      (node (ref "MCU1") (pin "129") (pinfunction "PG14_129") (pintype "bidirectional"))
    )
    (net (code "128") (name "unconnected-(MCU1-PG15-Pad132)") (class "Default")
      (node (ref "MCU1") (pin "132") (pinfunction "PG15_132") (pintype "bidirectional"))
    )
    (net (code "129") (name "unconnected-(P2-Pad7)") (class "Default")
      (node (ref "P2") (pin "7") (pinfunction "7_7") (pintype "passive+no_connect"))
    )
    (net (code "130") (name "unconnected-(P2-Pad8)") (class "Default")
      (node (ref "P2") (pin "8") (pinfunction "8_8") (pintype "passive+no_connect"))
    )
  )
)
